# Pulser.net
KiCad netlist of a schematic drawn in Altium Designer
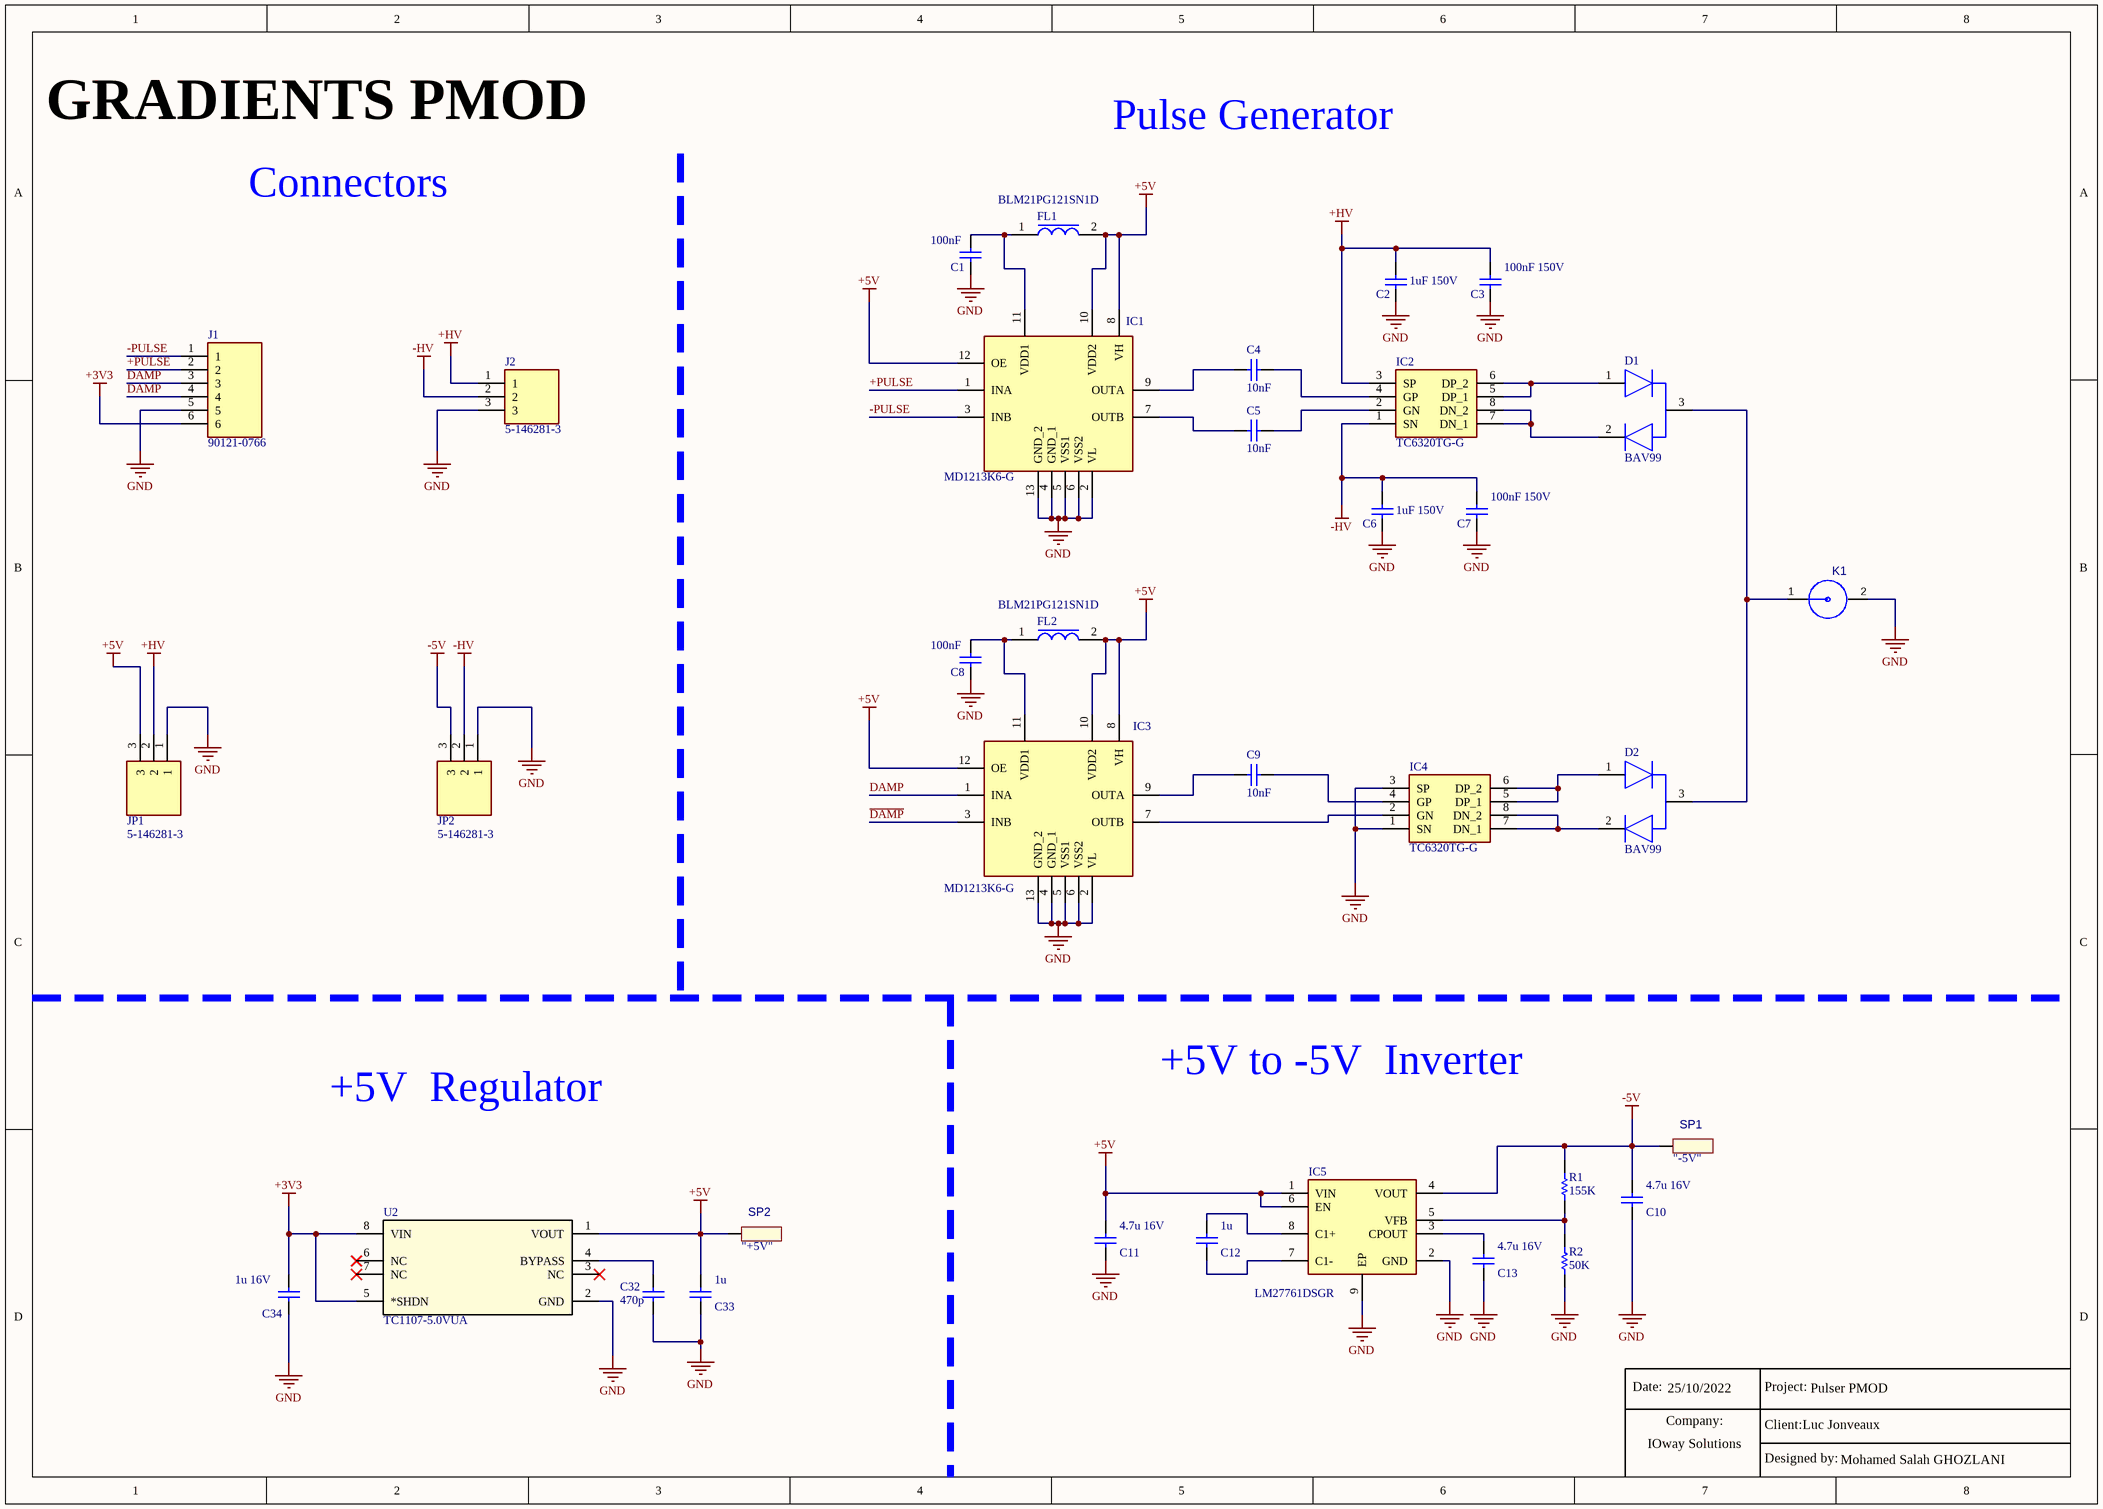
[diagram p0: Pulser.SchDoc]

(export (version "E")
  (design (tool "Eeschema 10.0.6"))
  (components
    (comp (ref "C1")
      (value "100nF")
      (footprint "SM0603 _3D_cap")
      (description "Capacitor  0603 inch")
      (fields (field (name "Comment") "cap0603") (field (name "PUBLISHER") "Altium Limited"))
      (libsource (lib "alt2017") (part "cap0603"))
    )
    (comp (ref "C2")
      (value "1uF 150V")
      (footprint "C1206")
      (description "Capacitor  0603 inch")
      (fields (field (name "Comment") "cap0603") (field (name "PUBLISHER") "Altium Limited"))
      (libsource (lib "alt2017") (part "cap0603"))
    )
    (comp (ref "C3")
      (value "100nF 150V")
      (footprint "C0805")
      (description "Capacitor  0603 inch")
      (fields (field (name "Comment") "cap0603") (field (name "PUBLISHER") "Altium Limited"))
      (libsource (lib "alt2017") (part "cap0603"))
    )
    (comp (ref "C4")
      (value "10nF")
      (footprint "SM0603 _3D_cap")
      (description "Capacitor  0603 inch")
      (fields (field (name "Comment") "cap0603") (field (name "PUBLISHER") "Altium Limited"))
      (libsource (lib "alt2017") (part "cap0603"))
    )
    (comp (ref "C5")
      (value "10nF")
      (footprint "SM0603 _3D_cap")
      (description "Capacitor  0603 inch")
      (fields (field (name "Comment") "cap0603") (field (name "PUBLISHER") "Altium Limited"))
      (libsource (lib "alt2017") (part "cap0603"))
    )
    (comp (ref "C6")
      (value "1uF 150V")
      (footprint "C1206")
      (description "Capacitor  0603 inch")
      (fields (field (name "Comment") "cap0603") (field (name "PUBLISHER") "Altium Limited"))
      (libsource (lib "alt2017") (part "cap0603"))
    )
    (comp (ref "C7")
      (value "100nF 150V")
      (footprint "C0805")
      (description "Capacitor  0603 inch")
      (fields (field (name "Comment") "cap0603") (field (name "PUBLISHER") "Altium Limited"))
      (libsource (lib "alt2017") (part "cap0603"))
    )
    (comp (ref "C8")
      (value "100nF")
      (footprint "SM0603 _3D_cap")
      (description "Capacitor  0603 inch")
      (fields (field (name "Comment") "cap0603") (field (name "PUBLISHER") "Altium Limited"))
      (libsource (lib "alt2017") (part "cap0603"))
    )
    (comp (ref "C9")
      (value "10nF")
      (footprint "SM0603 _3D_cap")
      (description "Capacitor  0603 inch")
      (fields (field (name "Comment") "cap0603") (field (name "PUBLISHER") "Altium Limited"))
      (libsource (lib "alt2017") (part "cap0603"))
    )
    (comp (ref "C10")
      (value "4.7u 16V")
      (footprint "SM0603 _3D_cap")
      (description "Capacitor  0603 inch")
      (fields (field (name "Comment") "cap0603") (field (name "PUBLISHER") "Altium Limited"))
      (libsource (lib "alt2017") (part "cap0603"))
    )
    (comp (ref "C11")
      (value "4.7u 16V")
      (footprint "SM0603 _3D_cap")
      (description "Capacitor  0603 inch")
      (fields (field (name "Comment") "cap0603") (field (name "PUBLISHER") "Altium Limited"))
      (libsource (lib "alt2017") (part "cap0603"))
    )
    (comp (ref "C12")
      (value "1u")
      (footprint "SM0603 _3D_cap")
      (description "Capacitor  0603 inch")
      (fields (field (name "Comment") "cap0603") (field (name "PUBLISHER") "Altium Limited"))
      (libsource (lib "alt2017") (part "cap0603"))
    )
    (comp (ref "C13")
      (value "4.7u 16V")
      (footprint "SM0603 _3D_cap")
      (description "Capacitor  0603 inch")
      (fields (field (name "Comment") "cap0603") (field (name "PUBLISHER") "Altium Limited"))
      (libsource (lib "alt2017") (part "cap0603"))
    )
    (comp (ref "C32")
      (value "470p")
      (footprint "0402_C")
      (description "Capacitor  0402 inch")
      (fields (field (name "Comment") "cap0402") (field (name "PUBLISHER") "Altium Limited"))
      (libsource (lib "alt2017") (part "cap0603"))
    )
    (comp (ref "C33")
      (value "1u")
      (footprint "SM0603 _3D_cap")
      (description "Capacitor  0603 inch")
      (fields (field (name "Comment") "cap0603") (field (name "PUBLISHER") "Altium Limited"))
      (libsource (lib "alt2017") (part "cap0603"))
    )
    (comp (ref "C34")
      (value "1u 16V")
      (footprint "SM0603 _3D_cap")
      (description "Capacitor  0603 inch")
      (fields (field (name "Comment") "cap0603") (field (name "PUBLISHER") "Altium Limited"))
      (libsource (lib "alt2017") (part "cap0603"))
    )
    (comp (ref "D1")
      (value "BAV99")
      (footprint "shunt_resistor:BAV99215")
      (description "Diode")
      (fields
        (field (name "MANUFACTURER_PART_NUMBER") "BAV99,215")
        (field (name "MOUSER PART NUMBER") "771-BAV99-T/R")
      )
      (libsource (lib "*") (part "BAV99,215"))
    )
    (comp (ref "D2")
      (value "BAV99")
      (footprint "shunt_resistor:BAV99215")
      (description "Diode")
      (fields
        (field (name "MANUFACTURER_PART_NUMBER") "BAV99,215")
        (field (name "MOUSER PART NUMBER") "771-BAV99-T/R")
      )
      (libsource (lib "*") (part "BAV99,215"))
    )
    (comp (ref "FL1")
      (value "BLM21PG121SN1D")
      (footprint "shunt_resistor:BLM21AG102BH1J")
      (description "Filter")
      (fields (field (name "MOUSER PART NUMBER") "81-BLM21PG121SN1D"))
      (libsource (lib "shunt_resistor") (part "BLM21PG121SN1D"))
    )
    (comp (ref "FL2")
      (value "BLM21PG121SN1D")
      (footprint "shunt_resistor:BLM21AG102BH1J")
      (description "Filter")
      (fields (field (name "MOUSER PART NUMBER") "81-BLM21PG121SN1D"))
      (libsource (lib "shunt_resistor") (part "BLM21PG121SN1D"))
    )
    (comp (ref "IC1")
      (value "MD1213K6-G")
      (footprint "shunt_resistor:QFN80P400X400X100-13N-D")
      (description "Integrated Circuit")
      (fields (field (name "MOUSER PART NUMBER") "689-MD1213K6-G"))
      (libsource (lib "shunt_resistor") (part "MD1213K6-G"))
    )
    (comp (ref "IC2")
      (value "TC6320TG-G")
      (footprint "shunt_resistor:SOIC127P600X175-8N")
      (description "Integrated Circuit")
      (fields (field (name "MOUSER PART NUMBER") "689-TC6320TG-G"))
      (libsource (lib "shunt_resistor") (part "TC6320TG-G"))
    )
    (comp (ref "IC3")
      (value "MD1213K6-G")
      (footprint "shunt_resistor:QFN80P400X400X100-13N-D")
      (description "Integrated Circuit")
      (fields (field (name "MOUSER PART NUMBER") "689-MD1213K6-G"))
      (libsource (lib "shunt_resistor") (part "MD1213K6-G"))
    )
    (comp (ref "IC4")
      (value "TC6320TG-G")
      (footprint "shunt_resistor:SOIC127P600X175-8N")
      (description "Integrated Circuit")
      (fields (field (name "MOUSER PART NUMBER") "689-TC6320TG-G"))
      (libsource (lib "shunt_resistor") (part "TC6320TG-G"))
    )
    (comp (ref "IC5")
      (value "LM27761DSGR")
      (footprint "shunt_resistor:SON50P200X200X80-9N")
      (description "Integrated Circuit")
      (fields (field (name "MOUSER PART NUMBER") "595-LM27761DSGR"))
      (libsource (lib "shunt_resistor") (part "LM27761DSGR"))
    )
    (comp (ref "J1")
      (value "90121-0766")
      (footprint "shunt_resistor:901210766")
      (description "Connector")
      (fields (field (name "MOUSER PART NUMBER") "538-90121-0766"))
      (libsource (lib "*") (part "90121-0766"))
    )
    (comp (ref "J2")
      (value "5-146281-3")
      (footprint "shunt_resistor:HDRV3W96P0X254_1X3_721X234X869P")
      (description "Connector")
      (fields (field (name "MOUSER PART NUMBER") "571-5-146281-3"))
      (libsource (lib "") (part "5-146281-3_1"))
    )
    (comp (ref "JP1")
      (value "5-146281-3")
      (footprint "shunt_resistor:HDRV3W96P0X254_1X3_721X234X869P")
      (description "Connector")
      (fields (field (name "MOUSER PART NUMBER") "571-5-146281-3"))
      (libsource (lib "*") (part "5-146281-3"))
    )
    (comp (ref "JP2")
      (value "5-146281-3")
      (footprint "shunt_resistor:HDRV3W96P0X254_1X3_721X234X869P")
      (description "Connector")
      (fields (field (name "MOUSER PART NUMBER") "571-5-146281-3"))
      (libsource (lib "*") (part "5-146281-3"))
    )
    (comp (ref "K1")
      (value "SMA_Edge")
      (footprint "AMPHENOL_132357-11")
      (libsource (lib "alt2017") (part "SMA_Edge"))
    )
    (comp (ref "R1")
      (value "155K")
      (footprint "1608[0603]")
      (description "Resistor")
      (fields (field (name "PUBLISHER") "Altium Limited"))
      (libsource (lib "Miscellaneous Devices") (part "Res1"))
    )
    (comp (ref "R2")
      (value "50K")
      (footprint "1608[0603]")
      (description "Resistor")
      (fields (field (name "PUBLISHER") "Altium Limited"))
      (libsource (lib "Miscellaneous Devices") (part "Res1"))
    )
    (comp (ref "SP1")
      (value "\"-5V\"")
      (footprint "SolderPad_D1mm _round")
      (description "for finger touch")
      (fields (field (name "Comment") "SolderPad D1mm_round"))
      (libsource (lib "alt2017") (part "SolderPad D1mm_round"))
    )
    (comp (ref "SP2")
      (value "\"+5V\"")
      (footprint "SolderPad_D1mm _round")
      (description "for finger touch")
      (fields (field (name "Comment") "SolderPad D1mm_round"))
      (libsource (lib "alt2017") (part "SolderPad D1mm_round"))
    )
    (comp (ref "U2")
      (value "TC1107-5.0VUA")
      (footprint "MSOP8_MC_MCH_")
      (description "No Description Available")
      (fields (field (name "COPYRIGHT") "Copyright (C) 2022 Ultra Librarian. All rights reserved."))
      (libsource (lib "TC1107-5P0VUA") (part "TC1107-5.0VUA"))
    )
  )
  (nets
    (net (code "1") (name "+3V3") (class "Default")
      (node (ref "C34") (pin "1") (pinfunction "1_1") (pintype "passive"))
      (node (ref "J1") (pin "6") (pinfunction "6_6") (pintype "passive"))
      (node (ref "U2") (pin "5") (pinfunction "*SHDN_5") (pintype "passive"))
      (node (ref "U2") (pin "8") (pinfunction "VIN_8") (pintype "passive"))
    )
    (net (code "2") (name "+5V") (class "Default")
      (node (ref "C11") (pin "1") (pinfunction "1_1") (pintype "passive"))
      (node (ref "C33") (pin "1") (pinfunction "1_1") (pintype "passive"))
      (node (ref "FL1") (pin "2") (pinfunction "2_2") (pintype "passive"))
      (node (ref "FL2") (pin "2") (pinfunction "2_2") (pintype "passive"))
      (node (ref "IC1") (pin "10") (pinfunction "VDD2_10") (pintype "passive"))
      (node (ref "IC1") (pin "12") (pinfunction "OE_12") (pintype "passive"))
      (node (ref "IC1") (pin "8") (pinfunction "VH_8") (pintype "passive"))
      (node (ref "IC3") (pin "10") (pinfunction "VDD2_10") (pintype "passive"))
      (node (ref "IC3") (pin "12") (pinfunction "OE_12") (pintype "passive"))
      (node (ref "IC3") (pin "8") (pinfunction "VH_8") (pintype "passive"))
      (node (ref "IC5") (pin "1") (pinfunction "VIN_1") (pintype "passive"))
      (node (ref "IC5") (pin "6") (pinfunction "EN_6") (pintype "passive"))
      (node (ref "JP1") (pin "3") (pinfunction "3_3") (pintype "passive"))
      (node (ref "SP2") (pin "1") (pinfunction "1_1") (pintype "passive"))
      (node (ref "U2") (pin "1") (pinfunction "VOUT_1") (pintype "passive"))
    )
    (net (code "3") (name "+HV") (class "Default")
      (node (ref "C2") (pin "1") (pinfunction "1_1") (pintype "passive"))
      (node (ref "C3") (pin "1") (pinfunction "1_1") (pintype "passive"))
      (node (ref "IC2") (pin "3") (pinfunction "SP_3") (pintype "passive"))
      (node (ref "J2") (pin "1") (pinfunction "1_1") (pintype "passive"))
      (node (ref "JP1") (pin "2") (pinfunction "2_2") (pintype "passive"))
    )
    (net (code "4") (name "-5V") (class "Default")
      (node (ref "C10") (pin "1") (pinfunction "1_1") (pintype "passive"))
      (node (ref "IC5") (pin "4") (pinfunction "VOUT_4") (pintype "passive"))
      (node (ref "JP2") (pin "3") (pinfunction "3_3") (pintype "passive"))
      (node (ref "R1") (pin "2") (pinfunction "2_2") (pintype "passive"))
      (node (ref "SP1") (pin "1") (pinfunction "1_1") (pintype "passive"))
    )
    (net (code "5") (name "-HV") (class "Default")
      (node (ref "C6") (pin "1") (pinfunction "1_1") (pintype "passive"))
      (node (ref "C7") (pin "1") (pinfunction "1_1") (pintype "passive"))
      (node (ref "IC2") (pin "1") (pinfunction "SN_1") (pintype "passive"))
      (node (ref "J2") (pin "2") (pinfunction "2_2") (pintype "passive"))
      (node (ref "JP2") (pin "2") (pinfunction "2_2") (pintype "passive"))
    )
    (net (code "6") (name "/+PULSE") (class "Default")
      (node (ref "IC1") (pin "1") (pinfunction "INA_1") (pintype "passive"))
      (node (ref "J1") (pin "2") (pinfunction "2_2") (pintype "passive"))
    )
    (net (code "7") (name "/-PULSE") (class "Default")
      (node (ref "IC1") (pin "3") (pinfunction "INB_3") (pintype "passive"))
      (node (ref "J1") (pin "1") (pinfunction "1_1") (pintype "passive"))
    )
    (net (code "8") (name "/DAMP") (class "Default")
      (node (ref "IC3") (pin "1") (pinfunction "INA_1") (pintype "passive"))
      (node (ref "J1") (pin "4") (pinfunction "4_4") (pintype "passive"))
    )
    (net (code "9") (name "/~{DAMP}") (class "Default")
      (node (ref "IC3") (pin "3") (pinfunction "INB_3") (pintype "passive"))
      (node (ref "J1") (pin "3") (pinfunction "3_3") (pintype "passive"))
    )
    (net (code "10") (name "GND") (class "Default")
      (node (ref "C1") (pin "2") (pinfunction "2_2") (pintype "passive"))
      (node (ref "C10") (pin "2") (pinfunction "2_2") (pintype "passive"))
      (node (ref "C11") (pin "2") (pinfunction "2_2") (pintype "passive"))
      (node (ref "C13") (pin "2") (pinfunction "2_2") (pintype "passive"))
      (node (ref "C2") (pin "2") (pinfunction "2_2") (pintype "passive"))
      (node (ref "C3") (pin "2") (pinfunction "2_2") (pintype "passive"))
      (node (ref "C32") (pin "1") (pinfunction "1_1") (pintype "passive"))
      (node (ref "C33") (pin "2") (pinfunction "2_2") (pintype "passive"))
      (node (ref "C34") (pin "2") (pinfunction "2_2") (pintype "passive"))
      (node (ref "C6") (pin "2") (pinfunction "2_2") (pintype "passive"))
      (node (ref "C7") (pin "2") (pinfunction "2_2") (pintype "passive"))
      (node (ref "C8") (pin "2") (pinfunction "2_2") (pintype "passive"))
      (node (ref "IC1") (pin "13") (pinfunction "GND_2_13") (pintype "passive"))
      (node (ref "IC1") (pin "2") (pinfunction "VL_2") (pintype "passive"))
      (node (ref "IC1") (pin "4") (pinfunction "GND_1_4") (pintype "passive"))
      (node (ref "IC1") (pin "5") (pinfunction "VSS1_5") (pintype "passive"))
      (node (ref "IC1") (pin "6") (pinfunction "VSS2_6") (pintype "passive"))
      (node (ref "IC3") (pin "13") (pinfunction "GND_2_13") (pintype "passive"))
      (node (ref "IC3") (pin "2") (pinfunction "VL_2") (pintype "passive"))
      (node (ref "IC3") (pin "4") (pinfunction "GND_1_4") (pintype "passive"))
      (node (ref "IC3") (pin "5") (pinfunction "VSS1_5") (pintype "passive"))
      (node (ref "IC3") (pin "6") (pinfunction "VSS2_6") (pintype "passive"))
      (node (ref "IC4") (pin "1") (pinfunction "SN_1") (pintype "passive"))
      (node (ref "IC4") (pin "3") (pinfunction "SP_3") (pintype "passive"))
      (node (ref "IC5") (pin "2") (pinfunction "GND_2") (pintype "passive"))
      (node (ref "IC5") (pin "9") (pinfunction "EP_9") (pintype "passive"))
      (node (ref "J1") (pin "5") (pinfunction "5_5") (pintype "passive"))
      (node (ref "J2") (pin "3") (pinfunction "3_3") (pintype "passive"))
      (node (ref "JP1") (pin "1") (pinfunction "1_1") (pintype "passive"))
      (node (ref "JP2") (pin "1") (pinfunction "1_1") (pintype "passive"))
      (node (ref "K1") (pin "2") (pinfunction "2_2") (pintype "passive"))
      (node (ref "R2") (pin "1") (pinfunction "1_1") (pintype "passive"))
      (node (ref "U2") (pin "2") (pinfunction "GND_2") (pintype "passive"))
    )
    (net (code "11") (name "Net-(D1-B)") (class "Default")
      (node (ref "D1") (pin "1") (pinfunction "B_1") (pintype "passive"))
      (node (ref "IC2") (pin "5") (pinfunction "DP_1_5") (pintype "passive"))
      (node (ref "IC2") (pin "6") (pinfunction "DP_2_6") (pintype "passive"))
    )
    (net (code "12") (name "Net-(D1-C)") (class "Default")
      (node (ref "D1") (pin "3") (pinfunction "C_3") (pintype "passive"))
      (node (ref "D2") (pin "3") (pinfunction "C_3") (pintype "passive"))
      (node (ref "K1") (pin "1") (pinfunction "1_1") (pintype "passive"))
    )
    (net (code "13") (name "Net-(D1-E)") (class "Default")
      (node (ref "D1") (pin "2") (pinfunction "E_2") (pintype "passive"))
      (node (ref "IC2") (pin "7") (pinfunction "DN_1_7") (pintype "passive"))
      (node (ref "IC2") (pin "8") (pinfunction "DN_2_8") (pintype "passive"))
    )
    (net (code "14") (name "Net-(D2-B)") (class "Default")
      (node (ref "D2") (pin "1") (pinfunction "B_1") (pintype "passive"))
      (node (ref "IC4") (pin "5") (pinfunction "DP_1_5") (pintype "passive"))
      (node (ref "IC4") (pin "6") (pinfunction "DP_2_6") (pintype "passive"))
    )
    (net (code "15") (name "Net-(D2-E)") (class "Default")
      (node (ref "D2") (pin "2") (pinfunction "E_2") (pintype "passive"))
      (node (ref "IC4") (pin "7") (pinfunction "DN_1_7") (pintype "passive"))
      (node (ref "IC4") (pin "8") (pinfunction "DN_2_8") (pintype "passive"))
    )
    (net (code "16") (name "Net-(IC1-OUTA)") (class "Default")
      (node (ref "C4") (pin "1") (pinfunction "1_1") (pintype "passive"))
      (node (ref "IC1") (pin "9") (pinfunction "OUTA_9") (pintype "passive"))
    )
    (net (code "17") (name "Net-(IC1-OUTB)") (class "Default")
      (node (ref "C5") (pin "1") (pinfunction "1_1") (pintype "passive"))
      (node (ref "IC1") (pin "7") (pinfunction "OUTB_7") (pintype "passive"))
    )
    (net (code "18") (name "Net-(IC1-VDD1)") (class "Default")
      (node (ref "C1") (pin "1") (pinfunction "1_1") (pintype "passive"))
      (node (ref "FL1") (pin "1") (pinfunction "1_1") (pintype "passive"))
      (node (ref "IC1") (pin "11") (pinfunction "VDD1_11") (pintype "passive"))
    )
    (net (code "19") (name "Net-(IC2-GN)") (class "Default")
      (node (ref "C5") (pin "2") (pinfunction "2_2") (pintype "passive"))
      (node (ref "IC2") (pin "2") (pinfunction "GN_2") (pintype "passive"))
    )
    (net (code "20") (name "Net-(IC2-GP)") (class "Default")
      (node (ref "C4") (pin "2") (pinfunction "2_2") (pintype "passive"))
      (node (ref "IC2") (pin "4") (pinfunction "GP_4") (pintype "passive"))
    )
    (net (code "21") (name "Net-(IC3-OUTA)") (class "Default")
      (node (ref "C9") (pin "1") (pinfunction "1_1") (pintype "passive"))
      (node (ref "IC3") (pin "9") (pinfunction "OUTA_9") (pintype "passive"))
    )
    (net (code "22") (name "Net-(IC3-OUTB)") (class "Default")
      (node (ref "IC3") (pin "7") (pinfunction "OUTB_7") (pintype "passive"))
      (node (ref "IC4") (pin "2") (pinfunction "GN_2") (pintype "passive"))
    )
    (net (code "23") (name "Net-(IC3-VDD1)") (class "Default")
      (node (ref "C8") (pin "1") (pinfunction "1_1") (pintype "passive"))
      (node (ref "FL2") (pin "1") (pinfunction "1_1") (pintype "passive"))
      (node (ref "IC3") (pin "11") (pinfunction "VDD1_11") (pintype "passive"))
    )
    (net (code "24") (name "Net-(IC4-GP)") (class "Default")
      (node (ref "C9") (pin "2") (pinfunction "2_2") (pintype "passive"))
      (node (ref "IC4") (pin "4") (pinfunction "GP_4") (pintype "passive"))
    )
    (net (code "25") (name "Net-(IC5-C1+)") (class "Default")
      (node (ref "C12") (pin "1") (pinfunction "1_1") (pintype "passive"))
      (node (ref "IC5") (pin "8") (pinfunction "C1+_8") (pintype "passive"))
    )
    (net (code "26") (name "Net-(IC5-C1-)") (class "Default")
      (node (ref "C12") (pin "2") (pinfunction "2_2") (pintype "passive"))
      (node (ref "IC5") (pin "7") (pinfunction "C1-_7") (pintype "passive"))
    )
    (net (code "27") (name "Net-(IC5-CPOUT)") (class "Default")
      (node (ref "C13") (pin "1") (pinfunction "1_1") (pintype "passive"))
      (node (ref "IC5") (pin "3") (pinfunction "CPOUT_3") (pintype "passive"))
    )
    (net (code "28") (name "Net-(IC5-VFB)") (class "Default")
      (node (ref "IC5") (pin "5") (pinfunction "VFB_5") (pintype "passive"))
      (node (ref "R1") (pin "1") (pinfunction "1_1") (pintype "passive"))
      (node (ref "R2") (pin "2") (pinfunction "2_2") (pintype "passive"))
    )
    (net (code "29") (name "Net-(U2-BYPASS)") (class "Default")
      (node (ref "C32") (pin "2") (pinfunction "2_2") (pintype "passive"))
      (node (ref "U2") (pin "4") (pinfunction "BYPASS_4") (pintype "passive"))
    )
    (net (code "30") (name "unconnected-(U2-NC-Pad3)") (class "Default")
      (node (ref "U2") (pin "3") (pinfunction "NC_3") (pintype "passive+no_connect"))
    )
    (net (code "31") (name "unconnected-(U2-NC-Pad6)") (class "Default")
      (node (ref "U2") (pin "6") (pinfunction "NC_6") (pintype "passive+no_connect"))
    )
    (net (code "32") (name "unconnected-(U2-NC-Pad7)") (class "Default")
      (node (ref "U2") (pin "7") (pinfunction "NC_7") (pintype "passive+no_connect"))
    )
  )
)
